# maxim.net
KiCad netlist of a schematic drawn in EAGLE
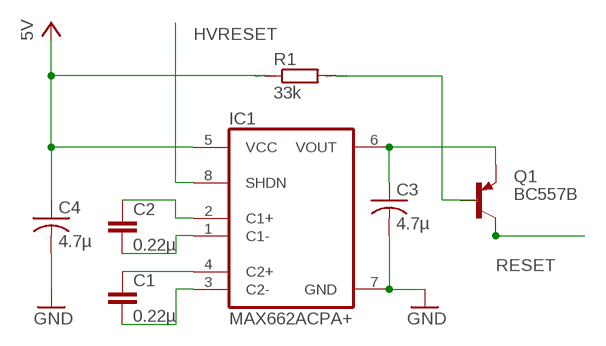
[diagram p0: schematic, sheet 1]

(export (version "E")
  (design (tool "Eeschema 10.0.6"))
  (components
    (comp (ref "C1")
      (value "0.22µ")
      (footprint "eagle-import:C025-024X044")
      (libsource (lib "eagle-import") (part "C-EU025-024X044"))
    )
    (comp (ref "C2")
      (value "0.22µ")
      (footprint "eagle-import:C025-024X044")
      (libsource (lib "eagle-import") (part "C-EU025-024X044"))
    )
    (comp (ref "C3")
      (value "4.7µ")
      (footprint "eagle-import:C025-024X044")
      (libsource (lib "eagle-import") (part "C-US025-024X044"))
    )
    (comp (ref "C4")
      (value "4.7µ")
      (footprint "eagle-import:C025-024X044")
      (libsource (lib "eagle-import") (part "C-US025-024X044"))
    )
    (comp (ref "IC1")
      (value "MAX662ACPA+")
      (footprint "eagle-import:DIL08")
      (libsource (lib "eagle-import") (part "MAX662CPA"))
    )
    (comp (ref "Q1")
      (value "BC557B")
      (footprint "eagle-import:TO92-EBC")
      (libsource (lib "eagle-import") (part "BC557B"))
    )
    (comp (ref "R1")
      (value "33k")
      (footprint "eagle-import:R0805")
      (libsource (lib "eagle-import") (part "R"))
    )
  )
  (nets
    (net (code "1") (name "/HVRESET") (class "Default")
      (node (ref "IC1") (pin "8") (pinfunction "SHDN_8") (pintype "input"))
    )
    (net (code "2") (name "/RESET") (class "Default")
      (node (ref "Q1") (pin "C") (pinfunction "C_C") (pintype "passive"))
    )
    (net (code "3") (name "5V") (class "Default")
      (node (ref "C4") (pin "1") (pinfunction "1_1") (pintype "passive"))
      (node (ref "IC1") (pin "5") (pinfunction "VCC_5") (pintype "power_in"))
      (node (ref "R1") (pin "1") (pinfunction "1_1") (pintype "passive"))
    )
    (net (code "4") (name "GND") (class "Default")
      (node (ref "C3") (pin "2") (pinfunction "2_2") (pintype "passive"))
      (node (ref "C4") (pin "2") (pinfunction "2_2") (pintype "passive"))
      (node (ref "IC1") (pin "7") (pinfunction "GND_7") (pintype "power_in"))
    )
    (net (code "5") (name "Net-(IC1-C1+)") (class "Default")
      (node (ref "C2") (pin "1") (pinfunction "1_1") (pintype "passive"))
      (node (ref "IC1") (pin "2") (pinfunction "C1+_2") (pintype "passive"))
    )
    (net (code "6") (name "Net-(IC1-C1-)") (class "Default")
      (node (ref "C2") (pin "2") (pinfunction "2_2") (pintype "passive"))
      (node (ref "IC1") (pin "1") (pinfunction "C1-_1") (pintype "passive"))
    )
    (net (code "7") (name "Net-(IC1-C2+)") (class "Default")
      (node (ref "C1") (pin "1") (pinfunction "1_1") (pintype "passive"))
      (node (ref "IC1") (pin "4") (pinfunction "C2+_4") (pintype "passive"))
    )
    (net (code "8") (name "Net-(IC1-C2-)") (class "Default")
      (node (ref "C1") (pin "2") (pinfunction "2_2") (pintype "passive"))
      (node (ref "IC1") (pin "3") (pinfunction "C2-_3") (pintype "passive"))
    )
    (net (code "9") (name "Net-(IC1-VOUT)") (class "Default")
      (node (ref "C3") (pin "1") (pinfunction "1_1") (pintype "passive"))
      (node (ref "IC1") (pin "6") (pinfunction "VOUT_6") (pintype "power_in"))
      (node (ref "Q1") (pin "E") (pinfunction "E_E") (pintype "passive"))
    )
    (net (code "10") (name "unconnected-(Q1-PadB)") (class "Default")
      (node (ref "Q1") (pin "B") (pinfunction "B_B") (pintype "passive"))
    )
    (net (code "11") (name "unconnected-(R1-Pad2)") (class "Default")
      (node (ref "R1") (pin "2") (pinfunction "2_2") (pintype "passive"))
    )
  )
)
